# 11_-BATTERY_BACKUP.net
KiCad netlist of a schematic drawn in Altium Designer
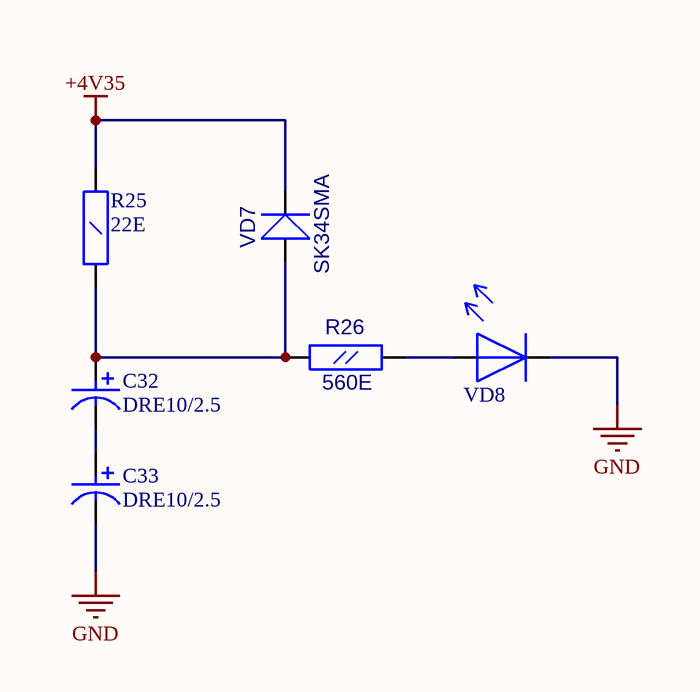
[diagram p0: [11]-BATTERY_BACKUP.SchDoc]

(export (version "E")
  (design (tool "Eeschema 10.0.6"))
  (components
    (comp (ref "C32")
      (value "DRE10/2.5")
      (footprint "CAP_D12.5_H25")
      (libsource (lib "fizik_lib") (part "SUPERCAP_10F"))
    )
    (comp (ref "C33")
      (value "DRE10/2.5")
      (footprint "CAP_D12.5_H25")
      (libsource (lib "fizik_lib") (part "SUPERCAP_10F"))
    )
    (comp (ref "R25")
      (value "22E")
      (footprint "R2512")
      (description "Resistor 2512 1W")
      (libsource (lib "fizik_lib") (part "RC2512"))
    )
    (comp (ref "R26")
      (value "560E")
      (footprint "RC0603")
      (description "RC0603")
      (libsource (lib "fizik_lib") (part "RC0603"))
    )
    (comp (ref "VD7")
      (value "SK34SMA")
      (footprint "SMA")
      (description "Schottky Rectifier")
      (libsource (lib "gprs_modem") (part "SK34SMA"))
    )
    (comp (ref "VD8")
      (value "LED_0805")
      (footprint "LED0805")
      (libsource (lib "fizik_lib") (part "LED_0805"))
    )
  )
  (nets
    (net (code "1") (name "+4V35") (class "Default")
      (node (ref "R25") (pin "2") (pinfunction "B_2") (pintype "passive"))
      (node (ref "VD7") (pin "2") (pinfunction "K_2") (pintype "passive"))
    )
    (net (code "2") (name "GND") (class "Default")
      (node (ref "C33") (pin "1") (pintype "passive"))
      (node (ref "VD8") (pin "2") (pintype "passive"))
    )
    (net (code "3") (name "Net-(C32-Pad1)") (class "Default")
      (node (ref "C32") (pin "1") (pintype "passive"))
      (node (ref "C33") (pin "2") (pintype "passive"))
    )
    (net (code "4") (name "Net-(R25-A)") (class "Default")
      (node (ref "C32") (pin "2") (pintype "passive"))
      (node (ref "R25") (pin "1") (pinfunction "A_1") (pintype "passive"))
      (node (ref "R26") (pin "1") (pinfunction "A_1") (pintype "passive"))
      (node (ref "VD7") (pin "1") (pinfunction "A_1") (pintype "passive"))
    )
    (net (code "5") (name "Net-(R26-B)") (class "Default")
      (node (ref "R26") (pin "2") (pinfunction "B_2") (pintype "passive"))
      (node (ref "VD8") (pin "1") (pintype "passive"))
    )
  )
)
